# cube.net
KiCad netlist of a schematic drawn in Altium Designer
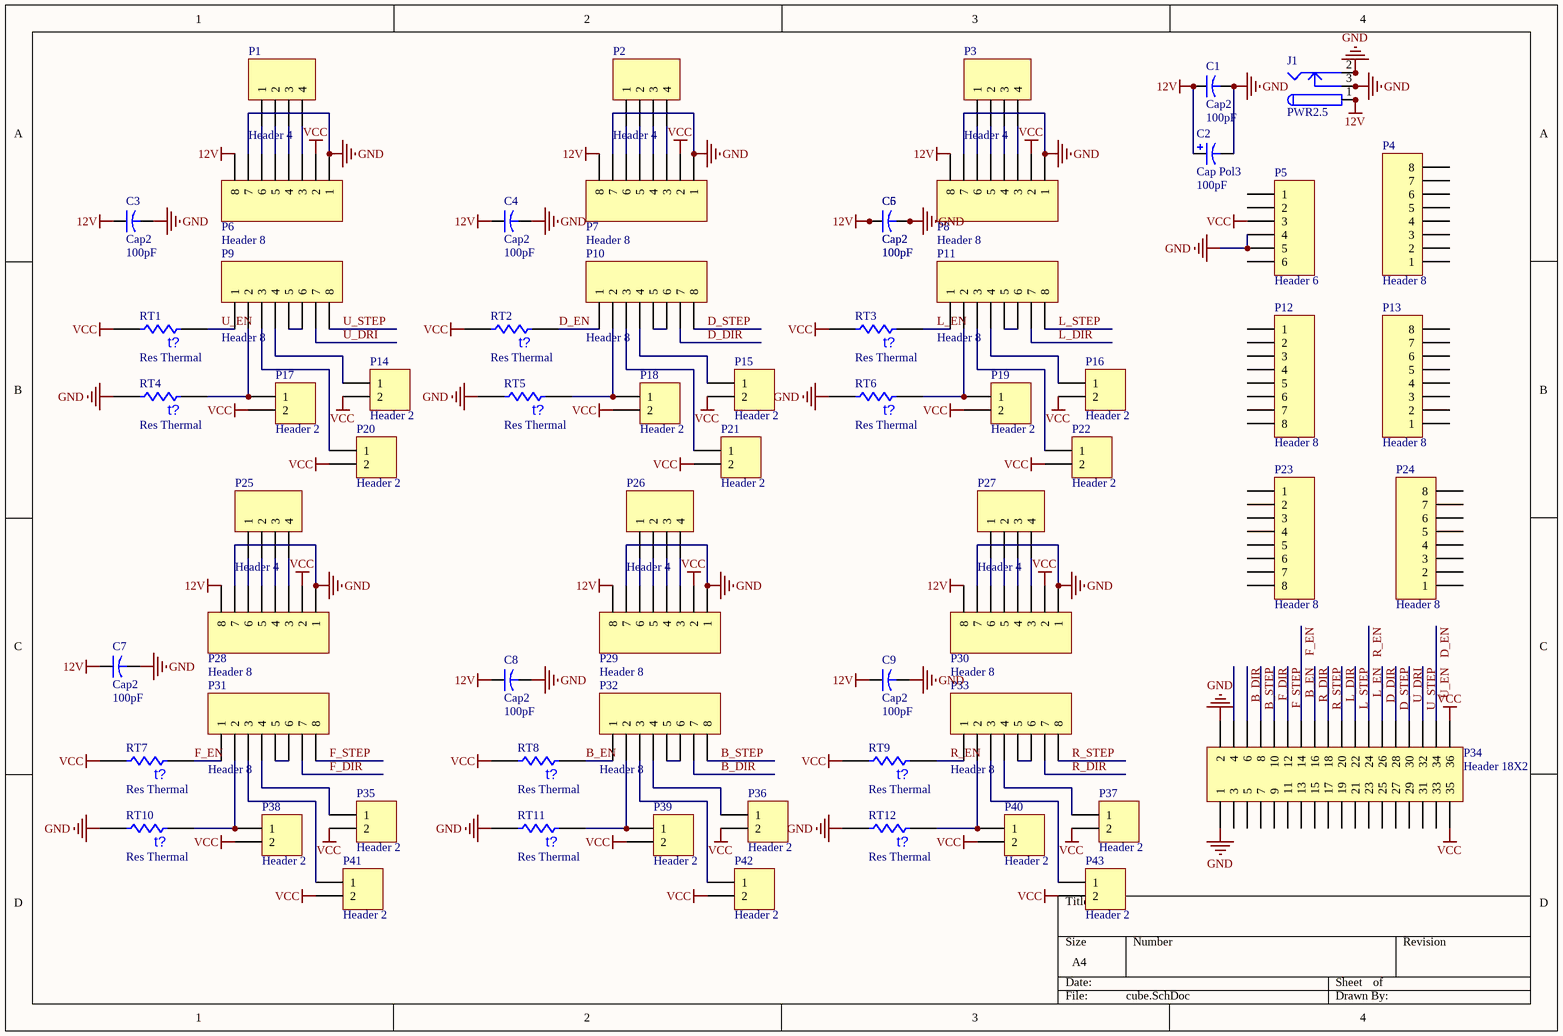
[diagram p0: cube.SchDoc]

(export (version "E")
  (design (tool "Eeschema 10.0.6"))
  (components
    (comp (ref "C1")
      (value "Cap2")
      (footprint "CAPR5-4X5")
      (description "Capacitor")
      (fields (field (name "ALTIUM_VALUE") "100pF") (field (name "PUBLISHER") "Altium Limited"))
      (libsource (lib "Miscellaneous Devices") (part "Cap2"))
    )
    (comp (ref "C2")
      (value "Cap Pol3")
      (footprint "1812")
      (description "Polarized Capacitor (Surface Mount)")
      (fields (field (name "ALTIUM_VALUE") "100pF") (field (name "PUBLISHER") "Altium Limited"))
      (libsource (lib "Miscellaneous Devices") (part "Cap Pol3"))
    )
    (comp (ref "C3")
      (value "Cap2")
      (footprint "CAPR5-4X5")
      (description "Capacitor")
      (fields (field (name "ALTIUM_VALUE") "100pF") (field (name "PUBLISHER") "Altium Limited"))
      (libsource (lib "Miscellaneous Devices") (part "Cap2"))
    )
    (comp (ref "C4")
      (value "Cap2")
      (footprint "CAPR5-4X5")
      (description "Capacitor")
      (fields (field (name "ALTIUM_VALUE") "100pF") (field (name "PUBLISHER") "Altium Limited"))
      (libsource (lib "Miscellaneous Devices") (part "Cap2"))
    )
    (comp (ref "C5")
      (value "Cap2")
      (footprint "CAPR5-4X5")
      (description "Capacitor")
      (fields (field (name "ALTIUM_VALUE") "100pF") (field (name "PUBLISHER") "Altium Limited"))
      (libsource (lib "Miscellaneous Devices") (part "Cap2"))
    )
    (comp (ref "C6")
      (value "Cap2")
      (footprint "CAPR5-4X5")
      (description "Capacitor")
      (fields (field (name "ALTIUM_VALUE") "100pF") (field (name "PUBLISHER") "Altium Limited"))
      (libsource (lib "Miscellaneous Devices") (part "Cap2"))
    )
    (comp (ref "C7")
      (value "Cap2")
      (footprint "CAPR5-4X5")
      (description "Capacitor")
      (fields (field (name "ALTIUM_VALUE") "100pF") (field (name "PUBLISHER") "Altium Limited"))
      (libsource (lib "Miscellaneous Devices") (part "Cap2"))
    )
    (comp (ref "C8")
      (value "Cap2")
      (footprint "CAPR5-4X5")
      (description "Capacitor")
      (fields (field (name "ALTIUM_VALUE") "100pF") (field (name "PUBLISHER") "Altium Limited"))
      (libsource (lib "Miscellaneous Devices") (part "Cap2"))
    )
    (comp (ref "C9")
      (value "Cap2")
      (footprint "CAPR5-4X5")
      (description "Capacitor")
      (fields (field (name "ALTIUM_VALUE") "100pF") (field (name "PUBLISHER") "Altium Limited"))
      (libsource (lib "Miscellaneous Devices") (part "Cap2"))
    )
    (comp (ref "J1")
      (value "PWR2.5")
      (footprint "KLD-0202")
      (description "Low Voltage Power Supply Connector")
      (fields (field (name "PUBLISHER") "Altium Limited"))
      (libsource (lib "Miscellaneous Connectors") (part "PWR2.5"))
    )
    (comp (ref "P1")
      (value "Header 4")
      (footprint "HDR1X4")
      (description "Header, 4-Pin")
      (fields (field (name "PUBLISHER") "Altium Limited"))
      (libsource (lib "Miscellaneous Connectors") (part "Header 4"))
    )
    (comp (ref "P2")
      (value "Header 4")
      (footprint "HDR1X4")
      (description "Header, 4-Pin")
      (fields (field (name "PUBLISHER") "Altium Limited"))
      (libsource (lib "Miscellaneous Connectors") (part "Header 4"))
    )
    (comp (ref "P3")
      (value "Header 4")
      (footprint "HDR1X4")
      (description "Header, 4-Pin")
      (fields (field (name "PUBLISHER") "Altium Limited"))
      (libsource (lib "Miscellaneous Connectors") (part "Header 4"))
    )
    (comp (ref "P4")
      (value "Header 8")
      (footprint "HDR1X8")
      (description "Header, 8-Pin")
      (fields (field (name "PUBLISHER") "Altium Limited"))
      (libsource (lib "Miscellaneous Connectors") (part "Header 8"))
    )
    (comp (ref "P5")
      (value "Header 6")
      (footprint "HDR1X6")
      (description "Header, 6-Pin")
      (fields (field (name "PUBLISHER") "Altium Limited"))
      (libsource (lib "Miscellaneous Connectors") (part "Header 6"))
    )
    (comp (ref "P6")
      (value "Header 8")
      (footprint "HDR1X8")
      (description "Header, 8-Pin")
      (fields (field (name "PUBLISHER") "Altium Limited"))
      (libsource (lib "") (part "Header 8_1"))
    )
    (comp (ref "P7")
      (value "Header 8")
      (footprint "HDR1X8")
      (description "Header, 8-Pin")
      (fields (field (name "PUBLISHER") "Altium Limited"))
      (libsource (lib "") (part "Header 8_1"))
    )
    (comp (ref "P8")
      (value "Header 8")
      (footprint "HDR1X8")
      (description "Header, 8-Pin")
      (fields (field (name "PUBLISHER") "Altium Limited"))
      (libsource (lib "") (part "Header 8_1"))
    )
    (comp (ref "P9")
      (value "Header 8")
      (footprint "HDR1X8")
      (description "Header, 8-Pin")
      (fields (field (name "PUBLISHER") "Altium Limited"))
      (libsource (lib "") (part "Header 8_2"))
    )
    (comp (ref "P10")
      (value "Header 8")
      (footprint "HDR1X8")
      (description "Header, 8-Pin")
      (fields (field (name "PUBLISHER") "Altium Limited"))
      (libsource (lib "") (part "Header 8_2"))
    )
    (comp (ref "P11")
      (value "Header 8")
      (footprint "HDR1X8")
      (description "Header, 8-Pin")
      (fields (field (name "PUBLISHER") "Altium Limited"))
      (libsource (lib "") (part "Header 8_2"))
    )
    (comp (ref "P12")
      (value "Header 8")
      (footprint "HDR1X8")
      (description "Header, 8-Pin")
      (fields (field (name "PUBLISHER") "Altium Limited"))
      (libsource (lib "") (part "Header 8_3"))
    )
    (comp (ref "P13")
      (value "Header 8")
      (footprint "HDR1X8")
      (description "Header, 8-Pin")
      (fields (field (name "PUBLISHER") "Altium Limited"))
      (libsource (lib "Miscellaneous Connectors") (part "Header 8"))
    )
    (comp (ref "P14")
      (value "Header 2")
      (footprint "HDR1X2")
      (description "Header, 2-Pin")
      (fields (field (name "PUBLISHER") "Altium Limited"))
      (libsource (lib "Miscellaneous Connectors") (part "Header 2"))
    )
    (comp (ref "P15")
      (value "Header 2")
      (footprint "HDR1X2")
      (description "Header, 2-Pin")
      (fields (field (name "PUBLISHER") "Altium Limited"))
      (libsource (lib "Miscellaneous Connectors") (part "Header 2"))
    )
    (comp (ref "P16")
      (value "Header 2")
      (footprint "HDR1X2")
      (description "Header, 2-Pin")
      (fields (field (name "PUBLISHER") "Altium Limited"))
      (libsource (lib "Miscellaneous Connectors") (part "Header 2"))
    )
    (comp (ref "P17")
      (value "Header 2")
      (footprint "HDR1X2")
      (description "Header, 2-Pin")
      (fields (field (name "PUBLISHER") "Altium Limited"))
      (libsource (lib "Miscellaneous Connectors") (part "Header 2"))
    )
    (comp (ref "P18")
      (value "Header 2")
      (footprint "HDR1X2")
      (description "Header, 2-Pin")
      (fields (field (name "PUBLISHER") "Altium Limited"))
      (libsource (lib "Miscellaneous Connectors") (part "Header 2"))
    )
    (comp (ref "P19")
      (value "Header 2")
      (footprint "HDR1X2")
      (description "Header, 2-Pin")
      (fields (field (name "PUBLISHER") "Altium Limited"))
      (libsource (lib "Miscellaneous Connectors") (part "Header 2"))
    )
    (comp (ref "P20")
      (value "Header 2")
      (footprint "HDR1X2")
      (description "Header, 2-Pin")
      (fields (field (name "PUBLISHER") "Altium Limited"))
      (libsource (lib "Miscellaneous Connectors") (part "Header 2"))
    )
    (comp (ref "P21")
      (value "Header 2")
      (footprint "HDR1X2")
      (description "Header, 2-Pin")
      (fields (field (name "PUBLISHER") "Altium Limited"))
      (libsource (lib "Miscellaneous Connectors") (part "Header 2"))
    )
    (comp (ref "P22")
      (value "Header 2")
      (footprint "HDR1X2")
      (description "Header, 2-Pin")
      (fields (field (name "PUBLISHER") "Altium Limited"))
      (libsource (lib "Miscellaneous Connectors") (part "Header 2"))
    )
    (comp (ref "P23")
      (value "Header 8")
      (footprint "HDR1X8")
      (description "Header, 8-Pin")
      (fields (field (name "PUBLISHER") "Altium Limited"))
      (libsource (lib "") (part "Header 8_3"))
    )
    (comp (ref "P24")
      (value "Header 8")
      (footprint "HDR1X8")
      (description "Header, 8-Pin")
      (fields (field (name "PUBLISHER") "Altium Limited"))
      (libsource (lib "Miscellaneous Connectors") (part "Header 8"))
    )
    (comp (ref "P25")
      (value "Header 4")
      (footprint "HDR1X4")
      (description "Header, 4-Pin")
      (fields (field (name "PUBLISHER") "Altium Limited"))
      (libsource (lib "Miscellaneous Connectors") (part "Header 4"))
    )
    (comp (ref "P26")
      (value "Header 4")
      (footprint "HDR1X4")
      (description "Header, 4-Pin")
      (fields (field (name "PUBLISHER") "Altium Limited"))
      (libsource (lib "Miscellaneous Connectors") (part "Header 4"))
    )
    (comp (ref "P27")
      (value "Header 4")
      (footprint "HDR1X4")
      (description "Header, 4-Pin")
      (fields (field (name "PUBLISHER") "Altium Limited"))
      (libsource (lib "Miscellaneous Connectors") (part "Header 4"))
    )
    (comp (ref "P28")
      (value "Header 8")
      (footprint "HDR1X8")
      (description "Header, 8-Pin")
      (fields (field (name "PUBLISHER") "Altium Limited"))
      (libsource (lib "") (part "Header 8_1"))
    )
    (comp (ref "P29")
      (value "Header 8")
      (footprint "HDR1X8")
      (description "Header, 8-Pin")
      (fields (field (name "PUBLISHER") "Altium Limited"))
      (libsource (lib "") (part "Header 8_1"))
    )
    (comp (ref "P30")
      (value "Header 8")
      (footprint "HDR1X8")
      (description "Header, 8-Pin")
      (fields (field (name "PUBLISHER") "Altium Limited"))
      (libsource (lib "") (part "Header 8_1"))
    )
    (comp (ref "P31")
      (value "Header 8")
      (footprint "HDR1X8")
      (description "Header, 8-Pin")
      (fields (field (name "PUBLISHER") "Altium Limited"))
      (libsource (lib "") (part "Header 8_2"))
    )
    (comp (ref "P32")
      (value "Header 8")
      (footprint "HDR1X8")
      (description "Header, 8-Pin")
      (fields (field (name "PUBLISHER") "Altium Limited"))
      (libsource (lib "") (part "Header 8_2"))
    )
    (comp (ref "P33")
      (value "Header 8")
      (footprint "HDR1X8")
      (description "Header, 8-Pin")
      (fields (field (name "PUBLISHER") "Altium Limited"))
      (libsource (lib "") (part "Header 8_2"))
    )
    (comp (ref "P34")
      (value "Header 18X2")
      (footprint "HDR2X18")
      (description "Header, 18-Pin, Dual row")
      (fields (field (name "PUBLISHER") "Altium Limited"))
      (libsource (lib "Miscellaneous Connectors") (part "Header 18X2"))
    )
    (comp (ref "P35")
      (value "Header 2")
      (footprint "HDR1X2")
      (description "Header, 2-Pin")
      (fields (field (name "PUBLISHER") "Altium Limited"))
      (libsource (lib "Miscellaneous Connectors") (part "Header 2"))
    )
    (comp (ref "P36")
      (value "Header 2")
      (footprint "HDR1X2")
      (description "Header, 2-Pin")
      (fields (field (name "PUBLISHER") "Altium Limited"))
      (libsource (lib "Miscellaneous Connectors") (part "Header 2"))
    )
    (comp (ref "P37")
      (value "Header 2")
      (footprint "HDR1X2")
      (description "Header, 2-Pin")
      (fields (field (name "PUBLISHER") "Altium Limited"))
      (libsource (lib "Miscellaneous Connectors") (part "Header 2"))
    )
    (comp (ref "P38")
      (value "Header 2")
      (footprint "HDR1X2")
      (description "Header, 2-Pin")
      (fields (field (name "PUBLISHER") "Altium Limited"))
      (libsource (lib "Miscellaneous Connectors") (part "Header 2"))
    )
    (comp (ref "P39")
      (value "Header 2")
      (footprint "HDR1X2")
      (description "Header, 2-Pin")
      (fields (field (name "PUBLISHER") "Altium Limited"))
      (libsource (lib "Miscellaneous Connectors") (part "Header 2"))
    )
    (comp (ref "P40")
      (value "Header 2")
      (footprint "HDR1X2")
      (description "Header, 2-Pin")
      (fields (field (name "PUBLISHER") "Altium Limited"))
      (libsource (lib "Miscellaneous Connectors") (part "Header 2"))
    )
    (comp (ref "P41")
      (value "Header 2")
      (footprint "HDR1X2")
      (description "Header, 2-Pin")
      (fields (field (name "PUBLISHER") "Altium Limited"))
      (libsource (lib "Miscellaneous Connectors") (part "Header 2"))
    )
    (comp (ref "P42")
      (value "Header 2")
      (footprint "HDR1X2")
      (description "Header, 2-Pin")
      (fields (field (name "PUBLISHER") "Altium Limited"))
      (libsource (lib "Miscellaneous Connectors") (part "Header 2"))
    )
    (comp (ref "P43")
      (value "Header 2")
      (footprint "HDR1X2")
      (description "Header, 2-Pin")
      (fields (field (name "PUBLISHER") "Altium Limited"))
      (libsource (lib "Miscellaneous Connectors") (part "Header 2"))
    )
    (comp (ref "RT1")
      (value "Res Thermal")
      (footprint "6-0805_L")
      (description "Thermistor")
      (fields (field (name "PUBLISHER") "Altium Limited"))
      (libsource (lib "Miscellaneous Devices") (part "Res Thermal"))
    )
    (comp (ref "RT2")
      (value "Res Thermal")
      (footprint "6-0805_L")
      (description "Thermistor")
      (fields (field (name "PUBLISHER") "Altium Limited"))
      (libsource (lib "Miscellaneous Devices") (part "Res Thermal"))
    )
    (comp (ref "RT3")
      (value "Res Thermal")
      (footprint "6-0805_L")
      (description "Thermistor")
      (fields (field (name "PUBLISHER") "Altium Limited"))
      (libsource (lib "Miscellaneous Devices") (part "Res Thermal"))
    )
    (comp (ref "RT4")
      (value "Res Thermal")
      (footprint "6-0805_L")
      (description "Thermistor")
      (fields (field (name "PUBLISHER") "Altium Limited"))
      (libsource (lib "Miscellaneous Devices") (part "Res Thermal"))
    )
    (comp (ref "RT5")
      (value "Res Thermal")
      (footprint "6-0805_L")
      (description "Thermistor")
      (fields (field (name "PUBLISHER") "Altium Limited"))
      (libsource (lib "Miscellaneous Devices") (part "Res Thermal"))
    )
    (comp (ref "RT6")
      (value "Res Thermal")
      (footprint "6-0805_L")
      (description "Thermistor")
      (fields (field (name "PUBLISHER") "Altium Limited"))
      (libsource (lib "Miscellaneous Devices") (part "Res Thermal"))
    )
    (comp (ref "RT7")
      (value "Res Thermal")
      (footprint "6-0805_L")
      (description "Thermistor")
      (fields (field (name "PUBLISHER") "Altium Limited"))
      (libsource (lib "Miscellaneous Devices") (part "Res Thermal"))
    )
    (comp (ref "RT8")
      (value "Res Thermal")
      (footprint "6-0805_L")
      (description "Thermistor")
      (fields (field (name "PUBLISHER") "Altium Limited"))
      (libsource (lib "Miscellaneous Devices") (part "Res Thermal"))
    )
    (comp (ref "RT9")
      (value "Res Thermal")
      (footprint "6-0805_L")
      (description "Thermistor")
      (fields (field (name "PUBLISHER") "Altium Limited"))
      (libsource (lib "Miscellaneous Devices") (part "Res Thermal"))
    )
    (comp (ref "RT10")
      (value "Res Thermal")
      (footprint "6-0805_L")
      (description "Thermistor")
      (fields (field (name "PUBLISHER") "Altium Limited"))
      (libsource (lib "Miscellaneous Devices") (part "Res Thermal"))
    )
    (comp (ref "RT11")
      (value "Res Thermal")
      (footprint "6-0805_L")
      (description "Thermistor")
      (fields (field (name "PUBLISHER") "Altium Limited"))
      (libsource (lib "Miscellaneous Devices") (part "Res Thermal"))
    )
    (comp (ref "RT12")
      (value "Res Thermal")
      (footprint "6-0805_L")
      (description "Thermistor")
      (fields (field (name "PUBLISHER") "Altium Limited"))
      (libsource (lib "Miscellaneous Devices") (part "Res Thermal"))
    )
  )
  (nets
    (net (code "1") (name "/B_DIR") (class "Default")
      (node (ref "P32") (pin "7") (pinfunction "7_7") (pintype "passive"))
      (node (ref "P34") (pin "6") (pinfunction "6_6") (pintype "passive"))
    )
    (net (code "2") (name "/B_EN") (class "Default")
      (node (ref "P31") (pin "1") (pinfunction "1_1") (pintype "passive"))
      (node (ref "P32") (pin "1") (pinfunction "1_1") (pintype "passive"))
      (node (ref "P34") (pin "14") (pinfunction "14_14") (pintype "passive"))
      (node (ref "RT7") (pin "1") (pinfunction "1_1") (pintype "passive"))
      (node (ref "RT8") (pin "1") (pinfunction "1_1") (pintype "passive"))
    )
    (net (code "3") (name "/B_STEP") (class "Default")
      (node (ref "P32") (pin "8") (pinfunction "8_8") (pintype "passive"))
      (node (ref "P34") (pin "8") (pinfunction "8_8") (pintype "passive"))
    )
    (net (code "4") (name "/D_DIR") (class "Default")
      (node (ref "P10") (pin "7") (pinfunction "7_7") (pintype "passive"))
      (node (ref "P34") (pin "26") (pinfunction "26_26") (pintype "passive"))
    )
    (net (code "5") (name "/D_EN") (class "Default")
      (node (ref "P10") (pin "1") (pinfunction "1_1") (pintype "passive"))
      (node (ref "P34") (pin "34") (pinfunction "34_34") (pintype "passive"))
      (node (ref "P9") (pin "1") (pinfunction "1_1") (pintype "passive"))
      (node (ref "RT1") (pin "1") (pinfunction "1_1") (pintype "passive"))
      (node (ref "RT2") (pin "1") (pinfunction "1_1") (pintype "passive"))
    )
    (net (code "6") (name "/D_STEP") (class "Default")
      (node (ref "P10") (pin "8") (pinfunction "8_8") (pintype "passive"))
      (node (ref "P34") (pin "28") (pinfunction "28_28") (pintype "passive"))
    )
    (net (code "7") (name "/F_DIR") (class "Default")
      (node (ref "P31") (pin "7") (pinfunction "7_7") (pintype "passive"))
      (node (ref "P34") (pin "10") (pinfunction "10_10") (pintype "passive"))
    )
    (net (code "8") (name "/F_STEP") (class "Default")
      (node (ref "P31") (pin "8") (pinfunction "8_8") (pintype "passive"))
      (node (ref "P34") (pin "12") (pinfunction "12_12") (pintype "passive"))
    )
    (net (code "9") (name "/L_DIR") (class "Default")
      (node (ref "P11") (pin "7") (pinfunction "7_7") (pintype "passive"))
      (node (ref "P34") (pin "20") (pinfunction "20_20") (pintype "passive"))
    )
    (net (code "10") (name "/L_EN") (class "Default")
      (node (ref "P11") (pin "1") (pinfunction "1_1") (pintype "passive"))
      (node (ref "P33") (pin "1") (pinfunction "1_1") (pintype "passive"))
      (node (ref "P34") (pin "24") (pinfunction "24_24") (pintype "passive"))
      (node (ref "RT3") (pin "1") (pinfunction "1_1") (pintype "passive"))
      (node (ref "RT9") (pin "1") (pinfunction "1_1") (pintype "passive"))
    )
    (net (code "11") (name "/L_STEP") (class "Default")
      (node (ref "P11") (pin "8") (pinfunction "8_8") (pintype "passive"))
      (node (ref "P34") (pin "22") (pinfunction "22_22") (pintype "passive"))
    )
    (net (code "12") (name "/R_DIR") (class "Default")
      (node (ref "P33") (pin "7") (pinfunction "7_7") (pintype "passive"))
      (node (ref "P34") (pin "16") (pinfunction "16_16") (pintype "passive"))
    )
    (net (code "13") (name "/R_STEP") (class "Default")
      (node (ref "P33") (pin "8") (pinfunction "8_8") (pintype "passive"))
      (node (ref "P34") (pin "18") (pinfunction "18_18") (pintype "passive"))
    )
    (net (code "14") (name "/U_DRI") (class "Default")
      (node (ref "P34") (pin "30") (pinfunction "30_30") (pintype "passive"))
      (node (ref "P9") (pin "7") (pinfunction "7_7") (pintype "passive"))
    )
    (net (code "15") (name "/U_STEP") (class "Default")
      (node (ref "P34") (pin "32") (pinfunction "32_32") (pintype "passive"))
      (node (ref "P9") (pin "8") (pinfunction "8_8") (pintype "passive"))
    )
    (net (code "16") (name "12V") (class "Default")
      (node (ref "C1") (pin "1") (pinfunction "1_1") (pintype "passive"))
      (node (ref "C2") (pin "1") (pinfunction "1_1") (pintype "passive"))
      (node (ref "C3") (pin "1") (pinfunction "1_1") (pintype "passive"))
      (node (ref "C4") (pin "1") (pinfunction "1_1") (pintype "passive"))
      (node (ref "C5") (pin "1") (pinfunction "1_1") (pintype "passive"))
      (node (ref "C6") (pin "1") (pinfunction "1_1") (pintype "passive"))
      (node (ref "C7") (pin "1") (pinfunction "1_1") (pintype "passive"))
      (node (ref "C8") (pin "1") (pinfunction "1_1") (pintype "passive"))
      (node (ref "C9") (pin "1") (pinfunction "1_1") (pintype "passive"))
      (node (ref "J1") (pin "1") (pinfunction "1_1") (pintype "power_in"))
      (node (ref "J1") (pin "1A") (pinfunction "1A_1A") (pintype "power_in"))
      (node (ref "J1") (pin "1B") (pinfunction "1B_1B") (pintype "power_in"))
      (node (ref "P28") (pin "8") (pinfunction "8_8") (pintype "passive"))
      (node (ref "P29") (pin "8") (pinfunction "8_8") (pintype "passive"))
      (node (ref "P30") (pin "8") (pinfunction "8_8") (pintype "passive"))
      (node (ref "P6") (pin "8") (pinfunction "8_8") (pintype "passive"))
      (node (ref "P7") (pin "8") (pinfunction "8_8") (pintype "passive"))
      (node (ref "P8") (pin "8") (pinfunction "8_8") (pintype "passive"))
    )
    (net (code "17") (name "GND") (class "Default")
      (node (ref "C1") (pin "2") (pinfunction "2_2") (pintype "passive"))
      (node (ref "C2") (pin "2") (pinfunction "2_2") (pintype "passive"))
      (node (ref "C3") (pin "2") (pinfunction "2_2") (pintype "passive"))
      (node (ref "C4") (pin "2") (pinfunction "2_2") (pintype "passive"))
      (node (ref "C5") (pin "2") (pinfunction "2_2") (pintype "passive"))
      (node (ref "C6") (pin "2") (pinfunction "2_2") (pintype "passive"))
      (node (ref "C7") (pin "2") (pinfunction "2_2") (pintype "passive"))
      (node (ref "C8") (pin "2") (pinfunction "2_2") (pintype "passive"))
      (node (ref "C9") (pin "2") (pinfunction "2_2") (pintype "passive"))
      (node (ref "J1") (pin "2") (pinfunction "2_2") (pintype "power_in"))
      (node (ref "J1") (pin "2A") (pinfunction "2A_2A") (pintype "power_in"))
      (node (ref "J1") (pin "2B") (pinfunction "2B_2B") (pintype "power_in"))
      (node (ref "J1") (pin "3") (pinfunction "3_3") (pintype "power_in"))
      (node (ref "J1") (pin "3A") (pinfunction "3A_3A") (pintype "power_in"))
      (node (ref "J1") (pin "3B") (pinfunction "3B_3B") (pintype "power_in"))
      (node (ref "P28") (pin "1") (pinfunction "1_1") (pintype "passive"))
      (node (ref "P28") (pin "7") (pinfunction "7_7") (pintype "passive"))
      (node (ref "P29") (pin "1") (pinfunction "1_1") (pintype "passive"))
      (node (ref "P29") (pin "7") (pinfunction "7_7") (pintype "passive"))
      (node (ref "P30") (pin "1") (pinfunction "1_1") (pintype "passive"))
      (node (ref "P30") (pin "7") (pinfunction "7_7") (pintype "passive"))
      (node (ref "P34") (pin "1") (pinfunction "1_1") (pintype "passive"))
      (node (ref "P34") (pin "2") (pinfunction "2_2") (pintype "passive"))
      (node (ref "P5") (pin "4") (pinfunction "4_4") (pintype "passive"))
      (node (ref "P5") (pin "5") (pinfunction "5_5") (pintype "passive"))
      (node (ref "P6") (pin "1") (pinfunction "1_1") (pintype "passive"))
      (node (ref "P6") (pin "7") (pinfunction "7_7") (pintype "passive"))
      (node (ref "P7") (pin "1") (pinfunction "1_1") (pintype "passive"))
      (node (ref "P7") (pin "7") (pinfunction "7_7") (pintype "passive"))
      (node (ref "P8") (pin "1") (pinfunction "1_1") (pintype "passive"))
      (node (ref "P8") (pin "7") (pinfunction "7_7") (pintype "passive"))
      (node (ref "RT10") (pin "2") (pinfunction "2_2") (pintype "passive"))
      (node (ref "RT11") (pin "2") (pinfunction "2_2") (pintype "passive"))
      (node (ref "RT12") (pin "2") (pinfunction "2_2") (pintype "passive"))
      (node (ref "RT4") (pin "2") (pinfunction "2_2") (pintype "passive"))
      (node (ref "RT5") (pin "2") (pinfunction "2_2") (pintype "passive"))
      (node (ref "RT6") (pin "2") (pinfunction "2_2") (pintype "passive"))
    )
    (net (code "18") (name "Net-(P1-Pad1)") (class "Default")
      (node (ref "P1") (pin "1") (pinfunction "1_1") (pintype "passive"))
      (node (ref "P6") (pin "6") (pinfunction "6_6") (pintype "passive"))
    )
    (net (code "19") (name "Net-(P1-Pad2)") (class "Default")
      (node (ref "P1") (pin "2") (pinfunction "2_2") (pintype "passive"))
      (node (ref "P6") (pin "5") (pinfunction "5_5") (pintype "passive"))
    )
    (net (code "20") (name "Net-(P1-Pad3)") (class "Default")
      (node (ref "P1") (pin "3") (pinfunction "3_3") (pintype "passive"))
      (node (ref "P6") (pin "4") (pinfunction "4_4") (pintype "passive"))
    )
    (net (code "21") (name "Net-(P1-Pad4)") (class "Default")
      (node (ref "P1") (pin "4") (pinfunction "4_4") (pintype "passive"))
      (node (ref "P6") (pin "3") (pinfunction "3_3") (pintype "passive"))
    )
    (net (code "22") (name "Net-(P2-Pad1)") (class "Default")
      (node (ref "P2") (pin "1") (pinfunction "1_1") (pintype "passive"))
      (node (ref "P7") (pin "6") (pinfunction "6_6") (pintype "passive"))
    )
    (net (code "23") (name "Net-(P2-Pad2)") (class "Default")
      (node (ref "P2") (pin "2") (pinfunction "2_2") (pintype "passive"))
      (node (ref "P7") (pin "5") (pinfunction "5_5") (pintype "passive"))
    )
    (net (code "24") (name "Net-(P2-Pad3)") (class "Default")
      (node (ref "P2") (pin "3") (pinfunction "3_3") (pintype "passive"))
      (node (ref "P7") (pin "4") (pinfunction "4_4") (pintype "passive"))
    )
    (net (code "25") (name "Net-(P2-Pad4)") (class "Default")
      (node (ref "P2") (pin "4") (pinfunction "4_4") (pintype "passive"))
      (node (ref "P7") (pin "3") (pinfunction "3_3") (pintype "passive"))
    )
    (net (code "26") (name "Net-(P3-Pad1)") (class "Default")
      (node (ref "P3") (pin "1") (pinfunction "1_1") (pintype "passive"))
      (node (ref "P8") (pin "6") (pinfunction "6_6") (pintype "passive"))
    )
    (net (code "27") (name "Net-(P3-Pad2)") (class "Default")
      (node (ref "P3") (pin "2") (pinfunction "2_2") (pintype "passive"))
      (node (ref "P8") (pin "5") (pinfunction "5_5") (pintype "passive"))
    )
    (net (code "28") (name "Net-(P3-Pad3)") (class "Default")
      (node (ref "P3") (pin "3") (pinfunction "3_3") (pintype "passive"))
      (node (ref "P8") (pin "4") (pinfunction "4_4") (pintype "passive"))
    )
    (net (code "29") (name "Net-(P3-Pad4)") (class "Default")
      (node (ref "P3") (pin "4") (pinfunction "4_4") (pintype "passive"))
      (node (ref "P8") (pin "3") (pinfunction "3_3") (pintype "passive"))
    )
    (net (code "30") (name "Net-(P9-Pad5)") (class "Default")
      (node (ref "P9") (pin "5") (pinfunction "5_5") (pintype "passive"))
      (node (ref "P9") (pin "6") (pinfunction "6_6") (pintype "passive"))
    )
    (net (code "31") (name "Net-(P10-Pad2)") (class "Default")
      (node (ref "P10") (pin "2") (pinfunction "2_2") (pintype "passive"))
      (node (ref "P18") (pin "1") (pinfunction "1_1") (pintype "passive"))
      (node (ref "RT5") (pin "1") (pinfunction "1_1") (pintype "passive"))
    )
    (net (code "32") (name "Net-(P10-Pad3)") (class "Default")
      (node (ref "P10") (pin "3") (pinfunction "3_3") (pintype "passive"))
      (node (ref "P21") (pin "1") (pinfunction "1_1") (pintype "passive"))
    )
    (net (code "33") (name "Net-(P10-Pad4)") (class "Default")
      (node (ref "P10") (pin "4") (pinfunction "4_4") (pintype "passive"))
      (node (ref "P15") (pin "1") (pinfunction "1_1") (pintype "passive"))
    )
    (net (code "34") (name "Net-(P10-Pad5)") (class "Default")
      (node (ref "P10") (pin "5") (pinfunction "5_5") (pintype "passive"))
      (node (ref "P10") (pin "6") (pinfunction "6_6") (pintype "passive"))
    )
    (net (code "35") (name "Net-(P11-Pad2)") (class "Default")
      (node (ref "P11") (pin "2") (pinfunction "2_2") (pintype "passive"))
      (node (ref "P19") (pin "1") (pinfunction "1_1") (pintype "passive"))
      (node (ref "RT6") (pin "1") (pinfunction "1_1") (pintype "passive"))
    )
    (net (code "36") (name "Net-(P11-Pad3)") (class "Default")
      (node (ref "P11") (pin "3") (pinfunction "3_3") (pintype "passive"))
      (node (ref "P22") (pin "1") (pinfunction "1_1") (pintype "passive"))
    )
    (net (code "37") (name "Net-(P11-Pad4)") (class "Default")
      (node (ref "P11") (pin "4") (pinfunction "4_4") (pintype "passive"))
      (node (ref "P16") (pin "1") (pinfunction "1_1") (pintype "passive"))
    )
    (net (code "38") (name "Net-(P11-Pad5)") (class "Default")
      (node (ref "P11") (pin "5") (pinfunction "5_5") (pintype "passive"))
      (node (ref "P11") (pin "6") (pinfunction "6_6") (pintype "passive"))
    )
    (net (code "39") (name "Net-(P14-Pad1)") (class "Default")
      (node (ref "P14") (pin "1") (pinfunction "1_1") (pintype "passive"))
      (node (ref "P9") (pin "4") (pinfunction "4_4") (pintype "passive"))
    )
    (net (code "40") (name "Net-(P17-Pad1)") (class "Default")
      (node (ref "P17") (pin "1") (pinfunction "1_1") (pintype "passive"))
      (node (ref "P9") (pin "2") (pinfunction "2_2") (pintype "passive"))
      (node (ref "RT4") (pin "1") (pinfunction "1_1") (pintype "passive"))
    )
    (net (code "41") (name "Net-(P20-Pad1)") (class "Default")
      (node (ref "P20") (pin "1") (pinfunction "1_1") (pintype "passive"))
      (node (ref "P9") (pin "3") (pinfunction "3_3") (pintype "passive"))
    )
    (net (code "42") (name "Net-(P25-Pad1)") (class "Default")
      (node (ref "P25") (pin "1") (pinfunction "1_1") (pintype "passive"))
      (node (ref "P28") (pin "6") (pinfunction "6_6") (pintype "passive"))
    )
    (net (code "43") (name "Net-(P25-Pad2)") (class "Default")
      (node (ref "P25") (pin "2") (pinfunction "2_2") (pintype "passive"))
      (node (ref "P28") (pin "5") (pinfunction "5_5") (pintype "passive"))
    )
    (net (code "44") (name "Net-(P25-Pad3)") (class "Default")
      (node (ref "P25") (pin "3") (pinfunction "3_3") (pintype "passive"))
      (node (ref "P28") (pin "4") (pinfunction "4_4") (pintype "passive"))
    )
    (net (code "45") (name "Net-(P25-Pad4)") (class "Default")
      (node (ref "P25") (pin "4") (pinfunction "4_4") (pintype "passive"))
      (node (ref "P28") (pin "3") (pinfunction "3_3") (pintype "passive"))
    )
    (net (code "46") (name "Net-(P26-Pad1)") (class "Default")
      (node (ref "P26") (pin "1") (pinfunction "1_1") (pintype "passive"))
      (node (ref "P29") (pin "6") (pinfunction "6_6") (pintype "passive"))
    )
    (net (code "47") (name "Net-(P26-Pad2)") (class "Default")
      (node (ref "P26") (pin "2") (pinfunction "2_2") (pintype "passive"))
      (node (ref "P29") (pin "5") (pinfunction "5_5") (pintype "passive"))
    )
    (net (code "48") (name "Net-(P26-Pad3)") (class "Default")
      (node (ref "P26") (pin "3") (pinfunction "3_3") (pintype "passive"))
      (node (ref "P29") (pin "4") (pinfunction "4_4") (pintype "passive"))
    )
    (net (code "49") (name "Net-(P26-Pad4)") (class "Default")
      (node (ref "P26") (pin "4") (pinfunction "4_4") (pintype "passive"))
      (node (ref "P29") (pin "3") (pinfunction "3_3") (pintype "passive"))
    )
    (net (code "50") (name "Net-(P27-Pad1)") (class "Default")
      (node (ref "P27") (pin "1") (pinfunction "1_1") (pintype "passive"))
      (node (ref "P30") (pin "6") (pinfunction "6_6") (pintype "passive"))
    )
    (net (code "51") (name "Net-(P27-Pad2)") (class "Default")
      (node (ref "P27") (pin "2") (pinfunction "2_2") (pintype "passive"))
      (node (ref "P30") (pin "5") (pinfunction "5_5") (pintype "passive"))
    )
    (net (code "52") (name "Net-(P27-Pad3)") (class "Default")
      (node (ref "P27") (pin "3") (pinfunction "3_3") (pintype "passive"))
      (node (ref "P30") (pin "4") (pinfunction "4_4") (pintype "passive"))
    )
    (net (code "53") (name "Net-(P27-Pad4)") (class "Default")
      (node (ref "P27") (pin "4") (pinfunction "4_4") (pintype "passive"))
      (node (ref "P30") (pin "3") (pinfunction "3_3") (pintype "passive"))
    )
    (net (code "54") (name "Net-(P31-Pad2)") (class "Default")
      (node (ref "P31") (pin "2") (pinfunction "2_2") (pintype "passive"))
      (node (ref "P38") (pin "1") (pinfunction "1_1") (pintype "passive"))
      (node (ref "RT10") (pin "1") (pinfunction "1_1") (pintype "passive"))
    )
    (net (code "55") (name "Net-(P31-Pad3)") (class "Default")
      (node (ref "P31") (pin "3") (pinfunction "3_3") (pintype "passive"))
      (node (ref "P41") (pin "1") (pinfunction "1_1") (pintype "passive"))
    )
    (net (code "56") (name "Net-(P31-Pad4)") (class "Default")
      (node (ref "P31") (pin "4") (pinfunction "4_4") (pintype "passive"))
      (node (ref "P35") (pin "1") (pinfunction "1_1") (pintype "passive"))
    )
    (net (code "57") (name "Net-(P31-Pad5)") (class "Default")
      (node (ref "P31") (pin "5") (pinfunction "5_5") (pintype "passive"))
      (node (ref "P31") (pin "6") (pinfunction "6_6") (pintype "passive"))
    )
    (net (code "58") (name "Net-(P32-Pad2)") (class "Default")
      (node (ref "P32") (pin "2") (pinfunction "2_2") (pintype "passive"))
      (node (ref "P39") (pin "1") (pinfunction "1_1") (pintype "passive"))
      (node (ref "RT11") (pin "1") (pinfunction "1_1") (pintype "passive"))
    )
    (net (code "59") (name "Net-(P32-Pad3)") (class "Default")
      (node (ref "P32") (pin "3") (pinfunction "3_3") (pintype "passive"))
      (node (ref "P42") (pin "1") (pinfunction "1_1") (pintype "passive"))
    )
    (net (code "60") (name "Net-(P32-Pad4)") (class "Default")
      (node (ref "P32") (pin "4") (pinfunction "4_4") (pintype "passive"))
      (node (ref "P36") (pin "1") (pinfunction "1_1") (pintype "passive"))
    )
    (net (code "61") (name "Net-(P32-Pad5)") (class "Default")
      (node (ref "P32") (pin "5") (pinfunction "5_5") (pintype "passive"))
      (node (ref "P32") (pin "6") (pinfunction "6_6") (pintype "passive"))
    )
    (net (code "62") (name "Net-(P33-Pad2)") (class "Default")
      (node (ref "P33") (pin "2") (pinfunction "2_2") (pintype "passive"))
      (node (ref "P40") (pin "1") (pinfunction "1_1") (pintype "passive"))
      (node (ref "RT12") (pin "1") (pinfunction "1_1") (pintype "passive"))
    )
    (net (code "63") (name "Net-(P33-Pad3)") (class "Default")
      (node (ref "P33") (pin "3") (pinfunction "3_3") (pintype "passive"))
      (node (ref "P43") (pin "1") (pinfunction "1_1") (pintype "passive"))
    )
    (net (code "64") (name "Net-(P33-Pad4)") (class "Default")
      (node (ref "P33") (pin "4") (pinfunction "4_4") (pintype "passive"))
      (node (ref "P37") (pin "1") (pinfunction "1_1") (pintype "passive"))
    )
    (net (code "65") (name "Net-(P33-Pad5)") (class "Default")
      (node (ref "P33") (pin "5") (pinfunction "5_5") (pintype "passive"))
      (node (ref "P33") (pin "6") (pinfunction "6_6") (pintype "passive"))
    )
    (net (code "66") (name "VCC") (class "Default")
      (node (ref "P14") (pin "2") (pinfunction "2_2") (pintype "passive"))
      (node (ref "P15") (pin "2") (pinfunction "2_2") (pintype "passive"))
      (node (ref "P16") (pin "2") (pinfunction "2_2") (pintype "passive"))
      (node (ref "P17") (pin "2") (pinfunction "2_2") (pintype "passive"))
      (node (ref "P18") (pin "2") (pinfunction "2_2") (pintype "passive"))
      (node (ref "P19") (pin "2") (pinfunction "2_2") (pintype "passive"))
      (node (ref "P20") (pin "2") (pinfunction "2_2") (pintype "passive"))
      (node (ref "P21") (pin "2") (pinfunction "2_2") (pintype "passive"))
      (node (ref "P22") (pin "2") (pinfunction "2_2") (pintype "passive"))
      (node (ref "P28") (pin "2") (pinfunction "2_2") (pintype "passive"))
      (node (ref "P29") (pin "2") (pinfunction "2_2") (pintype "passive"))
      (node (ref "P30") (pin "2") (pinfunction "2_2") (pintype "passive"))
      (node (ref "P34") (pin "35") (pinfunction "35_35") (pintype "passive"))
      (node (ref "P34") (pin "36") (pinfunction "36_36") (pintype "passive"))
      (node (ref "P35") (pin "2") (pinfunction "2_2") (pintype "passive"))
      (node (ref "P36") (pin "2") (pinfunction "2_2") (pintype "passive"))
      (node (ref "P37") (pin "2") (pinfunction "2_2") (pintype "passive"))
      (node (ref "P38") (pin "2") (pinfunction "2_2") (pintype "passive"))
      (node (ref "P39") (pin "2") (pinfunction "2_2") (pintype "passive"))
      (node (ref "P40") (pin "2") (pinfunction "2_2") (pintype "passive"))
      (node (ref "P41") (pin "2") (pinfunction "2_2") (pintype "passive"))
      (node (ref "P42") (pin "2") (pinfunction "2_2") (pintype "passive"))
      (node (ref "P43") (pin "2") (pinfunction "2_2") (pintype "passive"))
      (node (ref "P5") (pin "3") (pinfunction "3_3") (pintype "passive"))
      (node (ref "P6") (pin "2") (pinfunction "2_2") (pintype "passive"))
      (node (ref "P7") (pin "2") (pinfunction "2_2") (pintype "passive"))
      (node (ref "P8") (pin "2") (pinfunction "2_2") (pintype "passive"))
      (node (ref "RT1") (pin "2") (pinfunction "2_2") (pintype "passive"))
      (node (ref "RT2") (pin "2") (pinfunction "2_2") (pintype "passive"))
      (node (ref "RT3") (pin "2") (pinfunction "2_2") (pintype "passive"))
      (node (ref "RT7") (pin "2") (pinfunction "2_2") (pintype "passive"))
      (node (ref "RT8") (pin "2") (pinfunction "2_2") (pintype "passive"))
      (node (ref "RT9") (pin "2") (pinfunction "2_2") (pintype "passive"))
    )
    (net (code "67") (name "unconnected-(P4-Pad1)") (class "Default")
      (node (ref "P4") (pin "1") (pinfunction "1_1") (pintype "passive"))
    )
    (net (code "68") (name "unconnected-(P4-Pad2)") (class "Default")
      (node (ref "P4") (pin "2") (pinfunction "2_2") (pintype "passive"))
    )
    (net (code "69") (name "unconnected-(P4-Pad3)") (class "Default")
      (node (ref "P4") (pin "3") (pinfunction "3_3") (pintype "passive"))
    )
    (net (code "70") (name "unconnected-(P4-Pad4)") (class "Default")
      (node (ref "P4") (pin "4") (pinfunction "4_4") (pintype "passive"))
    )
    (net (code "71") (name "unconnected-(P4-Pad5)") (class "Default")
      (node (ref "P4") (pin "5") (pinfunction "5_5") (pintype "passive"))
    )
    (net (code "72") (name "unconnected-(P4-Pad6)") (class "Default")
      (node (ref "P4") (pin "6") (pinfunction "6_6") (pintype "passive"))
    )
    (net (code "73") (name "unconnected-(P4-Pad7)") (class "Default")
      (node (ref "P4") (pin "7") (pinfunction "7_7") (pintype "passive"))
    )
    (net (code "74") (name "unconnected-(P4-Pad8)") (class "Default")
      (node (ref "P4") (pin "8") (pinfunction "8_8") (pintype "passive"))
    )
    (net (code "75") (name "unconnected-(P5-Pad1)") (class "Default")
      (node (ref "P5") (pin "1") (pinfunction "1_1") (pintype "passive"))
    )
    (net (code "76") (name "unconnected-(P5-Pad2)") (class "Default")
      (node (ref "P5") (pin "2") (pinfunction "2_2") (pintype "passive"))
    )
    (net (code "77") (name "unconnected-(P5-Pad6)") (class "Default")
      (node (ref "P5") (pin "6") (pinfunction "6_6") (pintype "passive"))
    )
    (net (code "78") (name "unconnected-(P12-Pad1)") (class "Default")
      (node (ref "P12") (pin "1") (pinfunction "1_1") (pintype "passive"))
    )
    (net (code "79") (name "unconnected-(P12-Pad2)") (class "Default")
      (node (ref "P12") (pin "2") (pinfunction "2_2") (pintype "passive"))
    )
    (net (code "80") (name "unconnected-(P12-Pad3)") (class "Default")
      (node (ref "P12") (pin "3") (pinfunction "3_3") (pintype "passive"))
    )
    (net (code "81") (name "unconnected-(P12-Pad4)") (class "Default")
      (node (ref "P12") (pin "4") (pinfunction "4_4") (pintype "passive"))
    )
    (net (code "82") (name "unconnected-(P12-Pad5)") (class "Default")
      (node (ref "P12") (pin "5") (pinfunction "5_5") (pintype "passive"))
    )
    (net (code "83") (name "unconnected-(P12-Pad6)") (class "Default")
      (node (ref "P12") (pin "6") (pinfunction "6_6") (pintype "passive"))
    )
    (net (code "84") (name "unconnected-(P12-Pad7)") (class "Default")
      (node (ref "P12") (pin "7") (pinfunction "7_7") (pintype "passive"))
    )
    (net (code "85") (name "unconnected-(P12-Pad8)") (class "Default")
      (node (ref "P12") (pin "8") (pinfunction "8_8") (pintype "passive"))
    )
    (net (code "86") (name "unconnected-(P13-Pad1)") (class "Default")
      (node (ref "P13") (pin "1") (pinfunction "1_1") (pintype "passive"))
    )
    (net (code "87") (name "unconnected-(P13-Pad2)") (class "Default")
      (node (ref "P13") (pin "2") (pinfunction "2_2") (pintype "passive"))
    )
    (net (code "88") (name "unconnected-(P13-Pad3)") (class "Default")
      (node (ref "P13") (pin "3") (pinfunction "3_3") (pintype "passive"))
    )
    (net (code "89") (name "unconnected-(P13-Pad4)") (class "Default")
      (node (ref "P13") (pin "4") (pinfunction "4_4") (pintype "passive"))
    )
    (net (code "90") (name "unconnected-(P13-Pad5)") (class "Default")
      (node (ref "P13") (pin "5") (pinfunction "5_5") (pintype "passive"))
    )
    (net (code "91") (name "unconnected-(P13-Pad6)") (class "Default")
      (node (ref "P13") (pin "6") (pinfunction "6_6") (pintype "passive"))
    )
    (net (code "92") (name "unconnected-(P13-Pad7)") (class "Default")
      (node (ref "P13") (pin "7") (pinfunction "7_7") (pintype "passive"))
    )
    (net (code "93") (name "unconnected-(P13-Pad8)") (class "Default")
      (node (ref "P13") (pin "8") (pinfunction "8_8") (pintype "passive"))
    )
    (net (code "94") (name "unconnected-(P23-Pad1)") (class "Default")
      (node (ref "P23") (pin "1") (pinfunction "1_1") (pintype "passive"))
    )
    (net (code "95") (name "unconnected-(P23-Pad2)") (class "Default")
      (node (ref "P23") (pin "2") (pinfunction "2_2") (pintype "passive"))
    )
    (net (code "96") (name "unconnected-(P23-Pad3)") (class "Default")
      (node (ref "P23") (pin "3") (pinfunction "3_3") (pintype "passive"))
    )
    (net (code "97") (name "unconnected-(P23-Pad4)") (class "Default")
      (node (ref "P23") (pin "4") (pinfunction "4_4") (pintype "passive"))
    )
    (net (code "98") (name "unconnected-(P23-Pad5)") (class "Default")
      (node (ref "P23") (pin "5") (pinfunction "5_5") (pintype "passive"))
    )
    (net (code "99") (name "unconnected-(P23-Pad6)") (class "Default")
      (node (ref "P23") (pin "6") (pinfunction "6_6") (pintype "passive"))
    )
    (net (code "100") (name "unconnected-(P23-Pad7)") (class "Default")
      (node (ref "P23") (pin "7") (pinfunction "7_7") (pintype "passive"))
    )
    (net (code "101") (name "unconnected-(P23-Pad8)") (class "Default")
      (node (ref "P23") (pin "8") (pinfunction "8_8") (pintype "passive"))
    )
    (net (code "102") (name "unconnected-(P24-Pad1)") (class "Default")
      (node (ref "P24") (pin "1") (pinfunction "1_1") (pintype "passive"))
    )
    (net (code "103") (name "unconnected-(P24-Pad2)") (class "Default")
      (node (ref "P24") (pin "2") (pinfunction "2_2") (pintype "passive"))
    )
    (net (code "104") (name "unconnected-(P24-Pad3)") (class "Default")
      (node (ref "P24") (pin "3") (pinfunction "3_3") (pintype "passive"))
    )
    (net (code "105") (name "unconnected-(P24-Pad4)") (class "Default")
      (node (ref "P24") (pin "4") (pinfunction "4_4") (pintype "passive"))
    )
    (net (code "106") (name "unconnected-(P24-Pad5)") (class "Default")
      (node (ref "P24") (pin "5") (pinfunction "5_5") (pintype "passive"))
    )
    (net (code "107") (name "unconnected-(P24-Pad6)") (class "Default")
      (node (ref "P24") (pin "6") (pinfunction "6_6") (pintype "passive"))
    )
    (net (code "108") (name "unconnected-(P24-Pad7)") (class "Default")
      (node (ref "P24") (pin "7") (pinfunction "7_7") (pintype "passive"))
    )
    (net (code "109") (name "unconnected-(P24-Pad8)") (class "Default")
      (node (ref "P24") (pin "8") (pinfunction "8_8") (pintype "passive"))
    )
    (net (code "110") (name "unconnected-(P34-Pad3)") (class "Default")
      (node (ref "P34") (pin "3") (pinfunction "3_3") (pintype "passive"))
    )
    (net (code "111") (name "unconnected-(P34-Pad4)") (class "Default")
      (node (ref "P34") (pin "4") (pinfunction "4_4") (pintype "passive"))
    )
    (net (code "112") (name "unconnected-(P34-Pad5)") (class "Default")
      (node (ref "P34") (pin "5") (pinfunction "5_5") (pintype "passive"))
    )
    (net (code "113") (name "unconnected-(P34-Pad7)") (class "Default")
      (node (ref "P34") (pin "7") (pinfunction "7_7") (pintype "passive"))
    )
    (net (code "114") (name "unconnected-(P34-Pad9)") (class "Default")
      (node (ref "P34") (pin "9") (pinfunction "9_9") (pintype "passive"))
    )
    (net (code "115") (name "unconnected-(P34-Pad11)") (class "Default")
      (node (ref "P34") (pin "11") (pinfunction "11_11") (pintype "passive"))
    )
    (net (code "116") (name "unconnected-(P34-Pad13)") (class "Default")
      (node (ref "P34") (pin "13") (pinfunction "13_13") (pintype "passive"))
    )
    (net (code "117") (name "unconnected-(P34-Pad15)") (class "Default")
      (node (ref "P34") (pin "15") (pinfunction "15_15") (pintype "passive"))
    )
    (net (code "118") (name "unconnected-(P34-Pad17)") (class "Default")
      (node (ref "P34") (pin "17") (pinfunction "17_17") (pintype "passive"))
    )
    (net (code "119") (name "unconnected-(P34-Pad19)") (class "Default")
      (node (ref "P34") (pin "19") (pinfunction "19_19") (pintype "passive"))
    )
    (net (code "120") (name "unconnected-(P34-Pad21)") (class "Default")
      (node (ref "P34") (pin "21") (pinfunction "21_21") (pintype "passive"))
    )
    (net (code "121") (name "unconnected-(P34-Pad23)") (class "Default")
      (node (ref "P34") (pin "23") (pinfunction "23_23") (pintype "passive"))
    )
    (net (code "122") (name "unconnected-(P34-Pad25)") (class "Default")
      (node (ref "P34") (pin "25") (pinfunction "25_25") (pintype "passive"))
    )
    (net (code "123") (name "unconnected-(P34-Pad27)") (class "Default")
      (node (ref "P34") (pin "27") (pinfunction "27_27") (pintype "passive"))
    )
    (net (code "124") (name "unconnected-(P34-Pad29)") (class "Default")
      (node (ref "P34") (pin "29") (pinfunction "29_29") (pintype "passive"))
    )
    (net (code "125") (name "unconnected-(P34-Pad31)") (class "Default")
      (node (ref "P34") (pin "31") (pinfunction "31_31") (pintype "passive"))
    )
    (net (code "126") (name "unconnected-(P34-Pad33)") (class "Default")
      (node (ref "P34") (pin "33") (pinfunction "33_33") (pintype "passive"))
    )
  )
)
